# DIO.net
KiCad netlist of a schematic drawn in Altium Designer
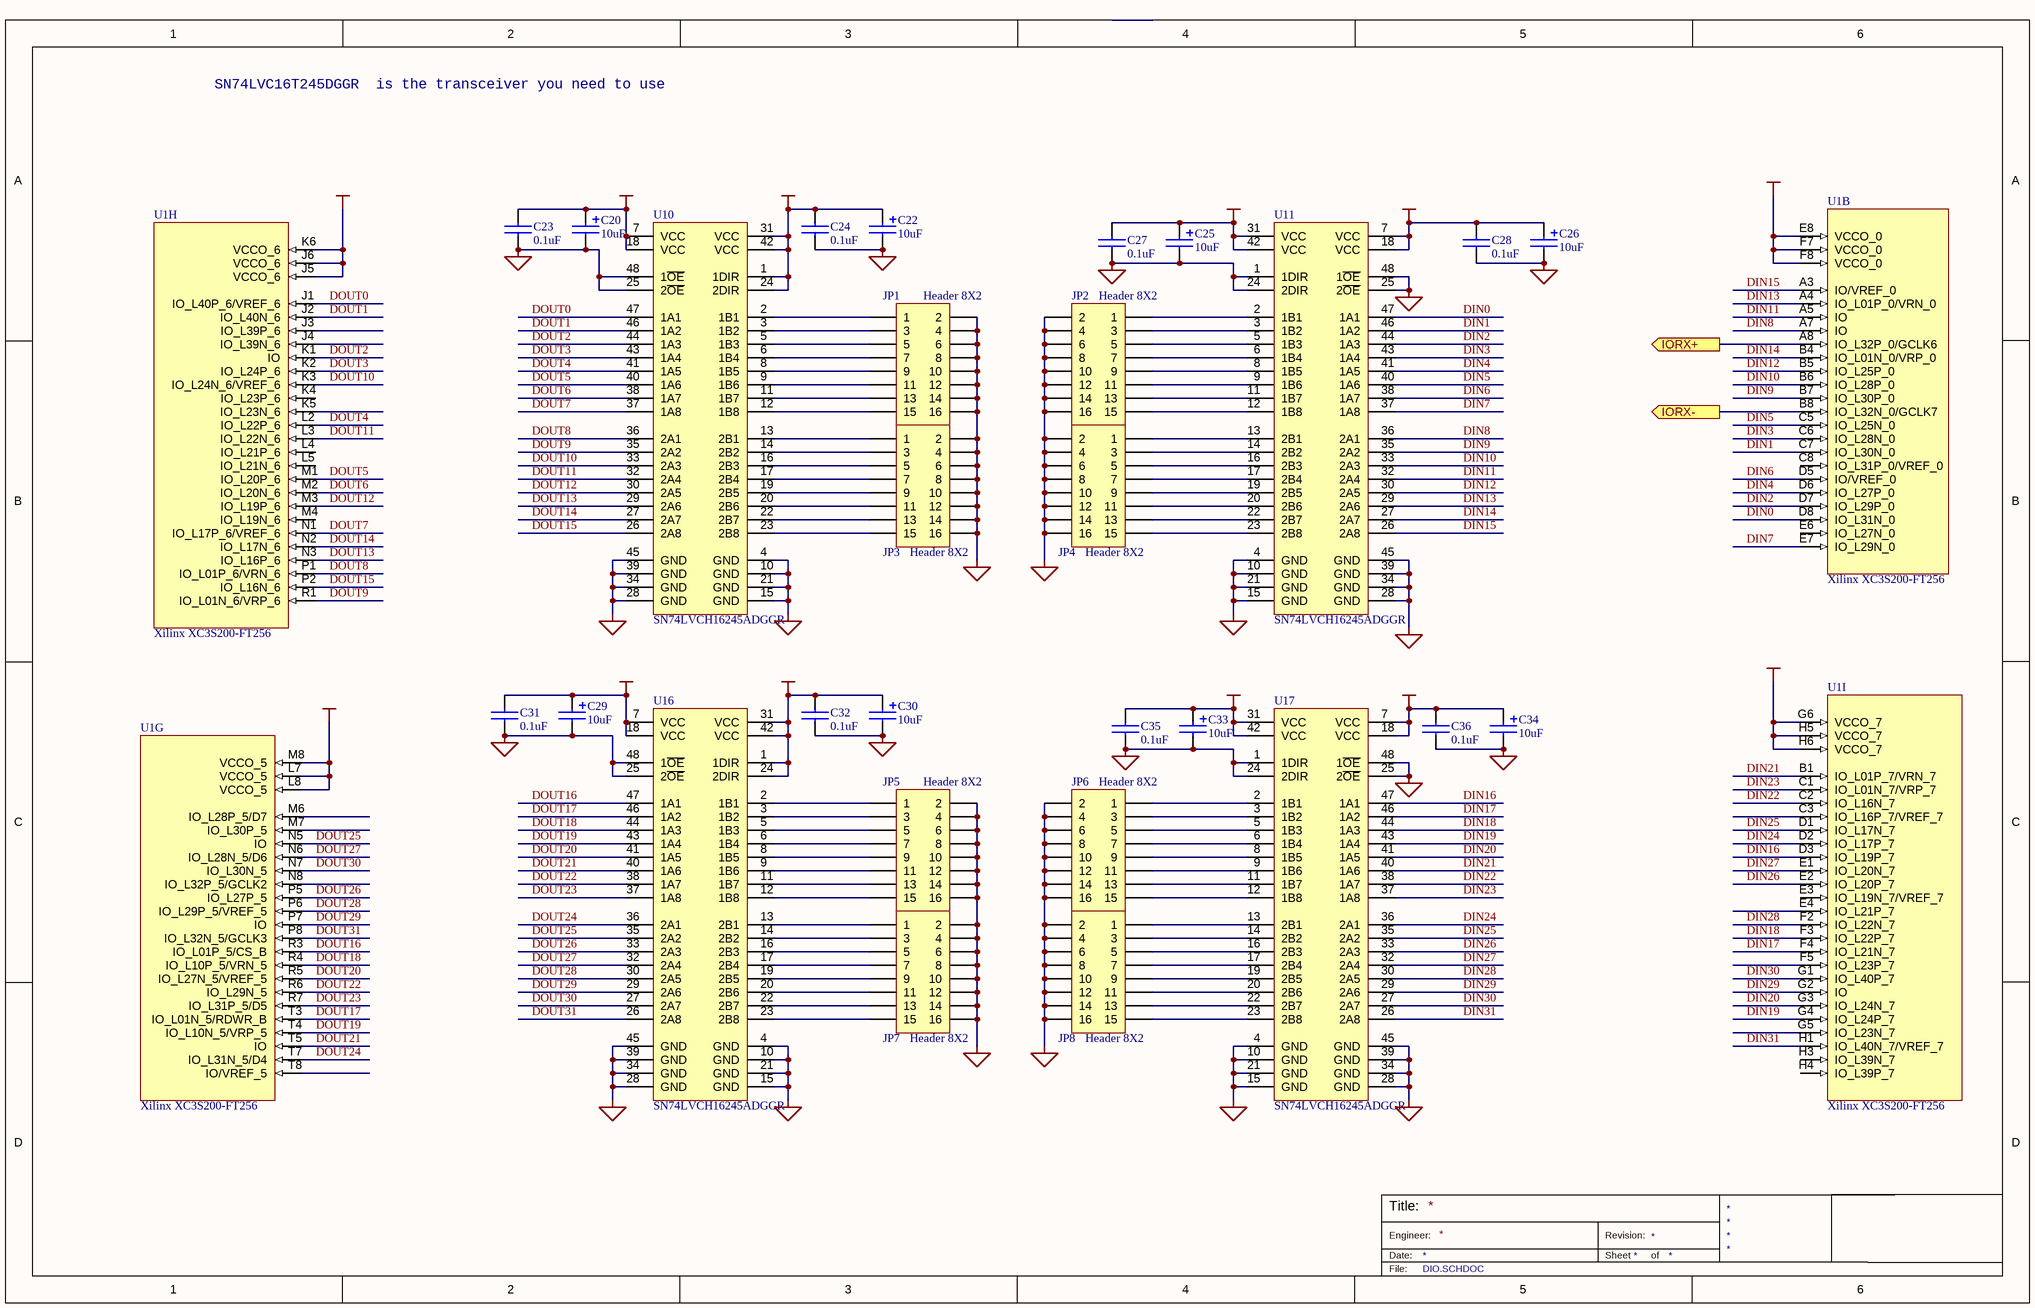
[diagram p0: DIO.SCHDOC]

(export (version "E")
  (design (tool "Eeschema 10.0.6"))
  (components
    (comp (ref "C20")
      (value "10uF")
      (footprint "3216")
      (description "Standard Capacitor")
      (fields (field (name "Comment") "POLCAP"))
      (libsource (lib "parts") (part "POLCAP"))
    )
    (comp (ref "C22")
      (value "10uF")
      (footprint "3216")
      (description "Standard Capacitor")
      (fields (field (name "Comment") "POLCAP"))
      (libsource (lib "parts") (part "POLCAP"))
    )
    (comp (ref "C23")
      (value "0.1uF")
      (footprint "0603")
      (description "Standard Capacitor")
      (fields (field (name "Comment") "CAPACITOR"))
      (libsource (lib "parts") (part "CAPACITOR"))
    )
    (comp (ref "C24")
      (value "0.1uF")
      (footprint "0603")
      (description "Standard Capacitor")
      (fields (field (name "Comment") "CAPACITOR"))
      (libsource (lib "parts") (part "CAPACITOR"))
    )
    (comp (ref "C25")
      (value "10uF")
      (footprint "3216")
      (description "Standard Capacitor")
      (fields (field (name "Comment") "POLCAP"))
      (libsource (lib "parts") (part "POLCAP"))
    )
    (comp (ref "C26")
      (value "10uF")
      (footprint "3216")
      (description "Standard Capacitor")
      (fields (field (name "Comment") "POLCAP"))
      (libsource (lib "parts") (part "POLCAP"))
    )
    (comp (ref "C27")
      (value "0.1uF")
      (footprint "0603")
      (description "Standard Capacitor")
      (fields (field (name "Comment") "CAPACITOR"))
      (libsource (lib "parts") (part "CAPACITOR"))
    )
    (comp (ref "C28")
      (value "0.1uF")
      (footprint "0603")
      (description "Standard Capacitor")
      (fields (field (name "Comment") "CAPACITOR"))
      (libsource (lib "parts") (part "CAPACITOR"))
    )
    (comp (ref "C29")
      (value "10uF")
      (footprint "3216")
      (description "Standard Capacitor")
      (fields (field (name "Comment") "POLCAP"))
      (libsource (lib "parts") (part "POLCAP"))
    )
    (comp (ref "C30")
      (value "10uF")
      (footprint "3216")
      (description "Standard Capacitor")
      (fields (field (name "Comment") "POLCAP"))
      (libsource (lib "parts") (part "POLCAP"))
    )
    (comp (ref "C31")
      (value "0.1uF")
      (footprint "0603")
      (description "Standard Capacitor")
      (fields (field (name "Comment") "CAPACITOR"))
      (libsource (lib "parts") (part "CAPACITOR"))
    )
    (comp (ref "C32")
      (value "0.1uF")
      (footprint "0603")
      (description "Standard Capacitor")
      (fields (field (name "Comment") "CAPACITOR"))
      (libsource (lib "parts") (part "CAPACITOR"))
    )
    (comp (ref "C33")
      (value "10uF")
      (footprint "3216")
      (description "Standard Capacitor")
      (fields (field (name "Comment") "POLCAP"))
      (libsource (lib "parts") (part "POLCAP"))
    )
    (comp (ref "C34")
      (value "10uF")
      (footprint "3216")
      (description "Standard Capacitor")
      (fields (field (name "Comment") "POLCAP"))
      (libsource (lib "parts") (part "POLCAP"))
    )
    (comp (ref "C35")
      (value "0.1uF")
      (footprint "0603")
      (description "Standard Capacitor")
      (fields (field (name "Comment") "CAPACITOR"))
      (libsource (lib "parts") (part "CAPACITOR"))
    )
    (comp (ref "C36")
      (value "0.1uF")
      (footprint "0603")
      (description "Standard Capacitor")
      (fields (field (name "Comment") "CAPACITOR"))
      (libsource (lib "parts") (part "CAPACITOR"))
    )
    (comp (ref "JP1")
      (value "Header 8X2")
      (footprint "HDR2X8")
      (description "Header, 8-Pin, Dual row")
      (fields (field (name "MANUFACTURER") "Generic Components") (field (name "PUBLISHER") "Altium Limited"))
      (libsource (lib "") (part "Header 8X2_1"))
    )
    (comp (ref "JP2")
      (value "Header 8X2")
      (footprint "HDR2X8")
      (description "Header, 8-Pin, Dual row")
      (fields (field (name "MANUFACTURER") "Generic Components") (field (name "PUBLISHER") "Altium Limited"))
      (libsource (lib "Miscellaneous Connectors") (part "Header 8X2"))
    )
    (comp (ref "JP3")
      (value "Header 8X2")
      (footprint "HDR2X8")
      (description "Header, 8-Pin, Dual row")
      (fields (field (name "MANUFACTURER") "Generic Components") (field (name "PUBLISHER") "Altium Limited"))
      (libsource (lib "") (part "Header 8X2_1"))
    )
    (comp (ref "JP4")
      (value "Header 8X2")
      (footprint "HDR2X8")
      (description "Header, 8-Pin, Dual row")
      (fields (field (name "MANUFACTURER") "Generic Components") (field (name "PUBLISHER") "Altium Limited"))
      (libsource (lib "Miscellaneous Connectors") (part "Header 8X2"))
    )
    (comp (ref "JP5")
      (value "Header 8X2")
      (footprint "HDR2X8")
      (description "Header, 8-Pin, Dual row")
      (fields (field (name "MANUFACTURER") "Generic Components") (field (name "PUBLISHER") "Altium Limited"))
      (libsource (lib "") (part "Header 8X2_1"))
    )
    (comp (ref "JP6")
      (value "Header 8X2")
      (footprint "HDR2X8")
      (description "Header, 8-Pin, Dual row")
      (fields (field (name "MANUFACTURER") "Generic Components") (field (name "PUBLISHER") "Altium Limited"))
      (libsource (lib "Miscellaneous Connectors") (part "Header 8X2"))
    )
    (comp (ref "JP7")
      (value "Header 8X2")
      (footprint "HDR2X8")
      (description "Header, 8-Pin, Dual row")
      (fields (field (name "MANUFACTURER") "Generic Components") (field (name "PUBLISHER") "Altium Limited"))
      (libsource (lib "") (part "Header 8X2_1"))
    )
    (comp (ref "JP8")
      (value "Header 8X2")
      (footprint "HDR2X8")
      (description "Header, 8-Pin, Dual row")
      (fields (field (name "MANUFACTURER") "Generic Components") (field (name "PUBLISHER") "Altium Limited"))
      (libsource (lib "Miscellaneous Connectors") (part "Header 8X2"))
    )
    (comp (ref "U1")
      (value "Xilinx XC3S200-FT256")
      (footprint "Xilinx FT256 BGA")
      (description "Xilinx Spartan-3 FPGA")
      (libsource (lib "") (part "XC3S200-FT256_1"))
    )
    (comp (ref "U10")
      (value "SN74LVCH16245ADGGR")
      (footprint "TSSO12x8-G48/X.3")
      (description "16-bit bus transceiver with 3-state outputs")
      (libsource (lib "") (part "SN74LVCH16245ADGGR_1"))
    )
    (comp (ref "U11")
      (value "SN74LVCH16245ADGGR")
      (footprint "TSSO12x8-G48/X.3")
      (description "16-bit bus transceiver with 3-state outputs")
      (libsource (lib "parts") (part "SN74LVCH16245ADGGR"))
    )
    (comp (ref "U16")
      (value "SN74LVCH16245ADGGR")
      (footprint "TSSO12x8-G48/X.3")
      (description "16-bit bus transceiver with 3-state outputs")
      (libsource (lib "") (part "SN74LVCH16245ADGGR_1"))
    )
    (comp (ref "U17")
      (value "SN74LVCH16245ADGGR")
      (footprint "TSSO12x8-G48/X.3")
      (description "16-bit bus transceiver with 3-state outputs")
      (libsource (lib "parts") (part "SN74LVCH16245ADGGR"))
    )
  )
  (nets
    (net (code "1") (name "+2.5VCC") (class "Default")
      (node (ref "C22") (pin "1") (pintype "passive"))
      (node (ref "C24") (pin "1") (pintype "passive"))
      (node (ref "C25") (pin "1") (pintype "passive"))
      (node (ref "C27") (pin "1") (pintype "passive"))
      (node (ref "C30") (pin "1") (pintype "passive"))
      (node (ref "C32") (pin "1") (pintype "passive"))
      (node (ref "C33") (pin "1") (pintype "passive"))
      (node (ref "C35") (pin "1") (pintype "passive"))
      (node (ref "U1") (pin "E8") (pinfunction "VCCO_0_E8") (pintype "input"))
      (node (ref "U1") (pin "F7") (pinfunction "VCCO_0_F7") (pintype "input"))
      (node (ref "U1") (pin "F8") (pinfunction "VCCO_0_F8") (pintype "input"))
      (node (ref "U1") (pin "G6") (pinfunction "VCCO_7_G6") (pintype "input"))
      (node (ref "U1") (pin "H5") (pinfunction "VCCO_7_H5") (pintype "input"))
      (node (ref "U1") (pin "H6") (pinfunction "VCCO_7_H6") (pintype "input"))
      (node (ref "U1") (pin "J5") (pinfunction "VCCO_6_J5") (pintype "input"))
      (node (ref "U1") (pin "J6") (pinfunction "VCCO_6_J6") (pintype "input"))
      (node (ref "U1") (pin "K6") (pinfunction "VCCO_6_K6") (pintype "input"))
      (node (ref "U1") (pin "L7") (pinfunction "VCCO_5_L7") (pintype "input"))
      (node (ref "U1") (pin "L8") (pinfunction "VCCO_5_L8") (pintype "input"))
      (node (ref "U1") (pin "M8") (pinfunction "VCCO_5_M8") (pintype "input"))
      (node (ref "U10") (pin "1") (pinfunction "1DIR_1") (pintype "passive"))
      (node (ref "U10") (pin "24") (pinfunction "2DIR_24") (pintype "passive"))
      (node (ref "U10") (pin "31") (pinfunction "VCC_31") (pintype "power_in"))
      (node (ref "U10") (pin "42") (pinfunction "VCC_42") (pintype "power_in"))
      (node (ref "U11") (pin "31") (pinfunction "VCC_31") (pintype "power_in"))
      (node (ref "U11") (pin "42") (pinfunction "VCC_42") (pintype "power_in"))
      (node (ref "U16") (pin "1") (pinfunction "1DIR_1") (pintype "passive"))
      (node (ref "U16") (pin "24") (pinfunction "2DIR_24") (pintype "passive"))
      (node (ref "U16") (pin "31") (pinfunction "VCC_31") (pintype "power_in"))
      (node (ref "U16") (pin "42") (pinfunction "VCC_42") (pintype "power_in"))
      (node (ref "U17") (pin "31") (pinfunction "VCC_31") (pintype "power_in"))
      (node (ref "U17") (pin "42") (pinfunction "VCC_42") (pintype "power_in"))
    )
    (net (code "2") (name "+5VCC") (class "Default")
      (node (ref "C20") (pin "1") (pintype "passive"))
      (node (ref "C23") (pin "1") (pintype "passive"))
      (node (ref "C26") (pin "1") (pintype "passive"))
      (node (ref "C28") (pin "1") (pintype "passive"))
      (node (ref "C29") (pin "1") (pintype "passive"))
      (node (ref "C31") (pin "1") (pintype "passive"))
      (node (ref "C34") (pin "1") (pintype "passive"))
      (node (ref "C36") (pin "1") (pintype "passive"))
      (node (ref "U10") (pin "18") (pinfunction "VCC_18") (pintype "power_in"))
      (node (ref "U10") (pin "7") (pinfunction "VCC_7") (pintype "power_in"))
      (node (ref "U11") (pin "18") (pinfunction "VCC_18") (pintype "power_in"))
      (node (ref "U11") (pin "7") (pinfunction "VCC_7") (pintype "power_in"))
      (node (ref "U16") (pin "18") (pinfunction "VCC_18") (pintype "power_in"))
      (node (ref "U16") (pin "7") (pinfunction "VCC_7") (pintype "power_in"))
      (node (ref "U17") (pin "18") (pinfunction "VCC_18") (pintype "power_in"))
      (node (ref "U17") (pin "7") (pinfunction "VCC_7") (pintype "power_in"))
    )
    (net (code "3") (name "/DIN0") (class "Default")
      (node (ref "U1") (pin "D8") (pinfunction "IO_L31N_0_D8") (pintype "input"))
      (node (ref "U11") (pin "47") (pinfunction "1A1_47") (pintype "passive"))
    )
    (net (code "4") (name "/DIN1") (class "Default")
      (node (ref "U1") (pin "C7") (pinfunction "IO_L30N_0_C7") (pintype "input"))
      (node (ref "U11") (pin "46") (pinfunction "1A2_46") (pintype "passive"))
    )
    (net (code "5") (name "/DIN2") (class "Default")
      (node (ref "U1") (pin "D7") (pinfunction "IO_L29P_0_D7") (pintype "input"))
      (node (ref "U11") (pin "44") (pinfunction "1A3_44") (pintype "passive"))
    )
    (net (code "6") (name "/DIN3") (class "Default")
      (node (ref "U1") (pin "C6") (pinfunction "IO_L28N_0_C6") (pintype "input"))
      (node (ref "U11") (pin "43") (pinfunction "1A4_43") (pintype "passive"))
    )
    (net (code "7") (name "/DIN4") (class "Default")
      (node (ref "U1") (pin "D6") (pinfunction "IO_L27P_0_D6") (pintype "input"))
      (node (ref "U11") (pin "41") (pinfunction "1A5_41") (pintype "passive"))
    )
    (net (code "8") (name "/DIN5") (class "Default")
      (node (ref "U1") (pin "C5") (pinfunction "IO_L25N_0_C5") (pintype "input"))
      (node (ref "U11") (pin "40") (pinfunction "1A6_40") (pintype "passive"))
    )
    (net (code "9") (name "/DIN6") (class "Default")
      (node (ref "U1") (pin "D5") (pinfunction "IO/VREF_0_D5") (pintype "input"))
      (node (ref "U11") (pin "38") (pinfunction "1A7_38") (pintype "passive"))
    )
    (net (code "10") (name "/DIN7") (class "Default")
      (node (ref "U1") (pin "E7") (pinfunction "IO_L29N_0_E7") (pintype "input"))
      (node (ref "U11") (pin "37") (pinfunction "1A8_37") (pintype "passive"))
    )
    (net (code "11") (name "/DIN8") (class "Default")
      (node (ref "U1") (pin "A7") (pinfunction "IO_A7") (pintype "input"))
      (node (ref "U11") (pin "36") (pinfunction "2A1_36") (pintype "passive"))
    )
    (net (code "12") (name "/DIN9") (class "Default")
      (node (ref "U1") (pin "B7") (pinfunction "IO_L30P_0_B7") (pintype "input"))
      (node (ref "U11") (pin "35") (pinfunction "2A2_35") (pintype "passive"))
    )
    (net (code "13") (name "/DIN10") (class "Default")
      (node (ref "U1") (pin "B6") (pinfunction "IO_L28P_0_B6") (pintype "input"))
      (node (ref "U11") (pin "33") (pinfunction "2A3_33") (pintype "passive"))
    )
    (net (code "14") (name "/DIN11") (class "Default")
      (node (ref "U1") (pin "A5") (pinfunction "IO_A5") (pintype "input"))
      (node (ref "U11") (pin "32") (pinfunction "2A4_32") (pintype "passive"))
    )
    (net (code "15") (name "/DIN12") (class "Default")
      (node (ref "U1") (pin "B5") (pinfunction "IO_L25P_0_B5") (pintype "input"))
      (node (ref "U11") (pin "30") (pinfunction "2A5_30") (pintype "passive"))
    )
    (net (code "16") (name "/DIN13") (class "Default")
      (node (ref "U1") (pin "A4") (pinfunction "IO_L01P_0/VRN_0_A4") (pintype "input"))
      (node (ref "U11") (pin "29") (pinfunction "2A6_29") (pintype "passive"))
    )
    (net (code "17") (name "/DIN14") (class "Default")
      (node (ref "U1") (pin "B4") (pinfunction "IO_L01N_0/VRP_0_B4") (pintype "input"))
      (node (ref "U11") (pin "27") (pinfunction "2A7_27") (pintype "passive"))
    )
    (net (code "18") (name "/DIN15") (class "Default")
      (node (ref "U1") (pin "A3") (pinfunction "IO/VREF_0_A3") (pintype "input"))
      (node (ref "U11") (pin "26") (pinfunction "2A8_26") (pintype "passive"))
    )
    (net (code "19") (name "/DIN16") (class "Default")
      (node (ref "U1") (pin "D3") (pinfunction "IO_L19P_7_D3") (pintype "input"))
      (node (ref "U17") (pin "47") (pinfunction "1A1_47") (pintype "passive"))
    )
    (net (code "20") (name "/DIN17") (class "Default")
      (node (ref "U1") (pin "F4") (pinfunction "IO_L21N_7_F4") (pintype "input"))
      (node (ref "U17") (pin "46") (pinfunction "1A2_46") (pintype "passive"))
    )
    (net (code "21") (name "/DIN18") (class "Default")
      (node (ref "U1") (pin "F3") (pinfunction "IO_L22P_7_F3") (pintype "input"))
      (node (ref "U17") (pin "44") (pinfunction "1A3_44") (pintype "passive"))
    )
    (net (code "22") (name "/DIN19") (class "Default")
      (node (ref "U1") (pin "G4") (pinfunction "IO_L24P_7_G4") (pintype "input"))
      (node (ref "U17") (pin "43") (pinfunction "1A4_43") (pintype "passive"))
    )
    (net (code "23") (name "/DIN20") (class "Default")
      (node (ref "U1") (pin "G3") (pinfunction "IO_L24N_7_G3") (pintype "input"))
      (node (ref "U17") (pin "41") (pinfunction "1A5_41") (pintype "passive"))
    )
    (net (code "24") (name "/DIN21") (class "Default")
      (node (ref "U1") (pin "B1") (pinfunction "IO_L01P_7/VRN_7_B1") (pintype "input"))
      (node (ref "U17") (pin "40") (pinfunction "1A6_40") (pintype "passive"))
    )
    (net (code "25") (name "/DIN22") (class "Default")
      (node (ref "U1") (pin "C2") (pinfunction "IO_L16N_7_C2") (pintype "input"))
      (node (ref "U17") (pin "38") (pinfunction "1A7_38") (pintype "passive"))
    )
    (net (code "26") (name "/DIN23") (class "Default")
      (node (ref "U1") (pin "C1") (pinfunction "IO_L01N_7/VRP_7_C1") (pintype "input"))
      (node (ref "U17") (pin "37") (pinfunction "1A8_37") (pintype "passive"))
    )
    (net (code "27") (name "/DIN24") (class "Default")
      (node (ref "U1") (pin "D2") (pinfunction "IO_L17P_7_D2") (pintype "input"))
      (node (ref "U17") (pin "36") (pinfunction "2A1_36") (pintype "passive"))
    )
    (net (code "28") (name "/DIN25") (class "Default")
      (node (ref "U1") (pin "D1") (pinfunction "IO_L17N_7_D1") (pintype "input"))
      (node (ref "U17") (pin "35") (pinfunction "2A2_35") (pintype "passive"))
    )
    (net (code "29") (name "/DIN26") (class "Default")
      (node (ref "U1") (pin "E2") (pinfunction "IO_L20P_7_E2") (pintype "input"))
      (node (ref "U17") (pin "33") (pinfunction "2A3_33") (pintype "passive"))
    )
    (net (code "30") (name "/DIN27") (class "Default")
      (node (ref "U1") (pin "E1") (pinfunction "IO_L20N_7_E1") (pintype "input"))
      (node (ref "U17") (pin "32") (pinfunction "2A4_32") (pintype "passive"))
    )
    (net (code "31") (name "/DIN28") (class "Default")
      (node (ref "U1") (pin "F2") (pinfunction "IO_L22N_7_F2") (pintype "input"))
      (node (ref "U17") (pin "30") (pinfunction "2A5_30") (pintype "passive"))
    )
    (net (code "32") (name "/DIN29") (class "Default")
      (node (ref "U1") (pin "G2") (pinfunction "IO_G2") (pintype "input"))
      (node (ref "U17") (pin "29") (pinfunction "2A6_29") (pintype "passive"))
    )
    (net (code "33") (name "/DIN30") (class "Default")
      (node (ref "U1") (pin "G1") (pinfunction "IO_L40P_7_G1") (pintype "input"))
      (node (ref "U17") (pin "27") (pinfunction "2A7_27") (pintype "passive"))
    )
    (net (code "34") (name "/DIN31") (class "Default")
      (node (ref "U1") (pin "H1") (pinfunction "IO_L40N_7/VREF_7_H1") (pintype "input"))
      (node (ref "U17") (pin "26") (pinfunction "2A8_26") (pintype "passive"))
    )
    (net (code "35") (name "/DOUT0") (class "Default")
      (node (ref "U1") (pin "J1") (pinfunction "IO_L40P_6/VREF_6_J1") (pintype "input"))
      (node (ref "U10") (pin "47") (pinfunction "1A1_47") (pintype "passive"))
    )
    (net (code "36") (name "/DOUT1") (class "Default")
      (node (ref "U1") (pin "J2") (pinfunction "IO_L40N_6_J2") (pintype "input"))
      (node (ref "U10") (pin "46") (pinfunction "1A2_46") (pintype "passive"))
    )
    (net (code "37") (name "/DOUT2") (class "Default")
      (node (ref "U1") (pin "K1") (pinfunction "IO_K1") (pintype "input"))
      (node (ref "U10") (pin "44") (pinfunction "1A3_44") (pintype "passive"))
    )
    (net (code "38") (name "/DOUT3") (class "Default")
      (node (ref "U1") (pin "K2") (pinfunction "IO_L24P_6_K2") (pintype "input"))
      (node (ref "U10") (pin "43") (pinfunction "1A4_43") (pintype "passive"))
    )
    (net (code "39") (name "/DOUT4") (class "Default")
      (node (ref "U1") (pin "L2") (pinfunction "IO_L22P_6_L2") (pintype "input"))
      (node (ref "U10") (pin "41") (pinfunction "1A5_41") (pintype "passive"))
    )
    (net (code "40") (name "/DOUT5") (class "Default")
      (node (ref "U1") (pin "M1") (pinfunction "IO_L20P_6_M1") (pintype "input"))
      (node (ref "U10") (pin "40") (pinfunction "1A6_40") (pintype "passive"))
    )
    (net (code "41") (name "/DOUT6") (class "Default")
      (node (ref "U1") (pin "M2") (pinfunction "IO_L20N_6_M2") (pintype "input"))
      (node (ref "U10") (pin "38") (pinfunction "1A7_38") (pintype "passive"))
    )
    (net (code "42") (name "/DOUT7") (class "Default")
      (node (ref "U1") (pin "N1") (pinfunction "IO_L17P_6/VREF_6_N1") (pintype "input"))
      (node (ref "U10") (pin "37") (pinfunction "1A8_37") (pintype "passive"))
    )
    (net (code "43") (name "/DOUT8") (class "Default")
      (node (ref "U1") (pin "P1") (pinfunction "IO_L01P_6/VRN_6_P1") (pintype "input"))
      (node (ref "U10") (pin "36") (pinfunction "2A1_36") (pintype "passive"))
    )
    (net (code "44") (name "/DOUT9") (class "Default")
      (node (ref "U1") (pin "R1") (pinfunction "IO_L01N_6/VRP_6_R1") (pintype "input"))
      (node (ref "U10") (pin "35") (pinfunction "2A2_35") (pintype "passive"))
    )
    (net (code "45") (name "/DOUT10") (class "Default")
      (node (ref "U1") (pin "K3") (pinfunction "IO_L24N_6/VREF_6_K3") (pintype "input"))
      (node (ref "U10") (pin "33") (pinfunction "2A3_33") (pintype "passive"))
    )
    (net (code "46") (name "/DOUT11") (class "Default")
      (node (ref "U1") (pin "L3") (pinfunction "IO_L22N_6_L3") (pintype "input"))
      (node (ref "U10") (pin "32") (pinfunction "2A4_32") (pintype "passive"))
    )
    (net (code "47") (name "/DOUT12") (class "Default")
      (node (ref "U1") (pin "M3") (pinfunction "IO_L19P_6_M3") (pintype "input"))
      (node (ref "U10") (pin "30") (pinfunction "2A5_30") (pintype "passive"))
    )
    (net (code "48") (name "/DOUT13") (class "Default")
      (node (ref "U1") (pin "N3") (pinfunction "IO_L16P_6_N3") (pintype "input"))
      (node (ref "U10") (pin "29") (pinfunction "2A6_29") (pintype "passive"))
    )
    (net (code "49") (name "/DOUT14") (class "Default")
      (node (ref "U1") (pin "N2") (pinfunction "IO_L17N_6_N2") (pintype "input"))
      (node (ref "U10") (pin "27") (pinfunction "2A7_27") (pintype "passive"))
    )
    (net (code "50") (name "/DOUT15") (class "Default")
      (node (ref "U1") (pin "P2") (pinfunction "IO_L16N_6_P2") (pintype "input"))
      (node (ref "U10") (pin "26") (pinfunction "2A8_26") (pintype "passive"))
    )
    (net (code "51") (name "/DOUT16") (class "Default")
      (node (ref "U1") (pin "R3") (pinfunction "IO_L01P_5/CS_B_R3") (pintype "input"))
      (node (ref "U16") (pin "47") (pinfunction "1A1_47") (pintype "passive"))
    )
    (net (code "52") (name "/DOUT17") (class "Default")
      (node (ref "U1") (pin "T3") (pinfunction "IO_L01N_5/RDWR_B_T3") (pintype "input"))
      (node (ref "U16") (pin "46") (pinfunction "1A2_46") (pintype "passive"))
    )
    (net (code "53") (name "/DOUT18") (class "Default")
      (node (ref "U1") (pin "R4") (pinfunction "IO_L10P_5/VRN_5_R4") (pintype "input"))
      (node (ref "U16") (pin "44") (pinfunction "1A3_44") (pintype "passive"))
    )
    (net (code "54") (name "/DOUT19") (class "Default")
      (node (ref "U1") (pin "T4") (pinfunction "IO_L10N_5/VRP_5_T4") (pintype "input"))
      (node (ref "U16") (pin "43") (pinfunction "1A4_43") (pintype "passive"))
    )
    (net (code "55") (name "/DOUT20") (class "Default")
      (node (ref "U1") (pin "R5") (pinfunction "IO_L27N_5/VREF_5_R5") (pintype "input"))
      (node (ref "U16") (pin "41") (pinfunction "1A5_41") (pintype "passive"))
    )
    (net (code "56") (name "/DOUT21") (class "Default")
      (node (ref "U1") (pin "T5") (pinfunction "IO_T5") (pintype "input"))
      (node (ref "U16") (pin "40") (pinfunction "1A6_40") (pintype "passive"))
    )
    (net (code "57") (name "/DOUT22") (class "Default")
      (node (ref "U1") (pin "R6") (pinfunction "IO_L29N_5_R6") (pintype "input"))
      (node (ref "U16") (pin "38") (pinfunction "1A7_38") (pintype "passive"))
    )
    (net (code "58") (name "/DOUT23") (class "Default")
      (node (ref "U1") (pin "R7") (pinfunction "IO_L31P_5/D5_R7") (pintype "input"))
      (node (ref "U16") (pin "37") (pinfunction "1A8_37") (pintype "passive"))
    )
    (net (code "59") (name "/DOUT24") (class "Default")
      (node (ref "U1") (pin "T7") (pinfunction "IO_L31N_5/D4_T7") (pintype "input"))
      (node (ref "U16") (pin "36") (pinfunction "2A1_36") (pintype "passive"))
    )
    (net (code "60") (name "/DOUT25") (class "Default")
      (node (ref "U1") (pin "N5") (pinfunction "IO_N5") (pintype "input"))
      (node (ref "U16") (pin "35") (pinfunction "2A2_35") (pintype "passive"))
    )
    (net (code "61") (name "/DOUT26") (class "Default")
      (node (ref "U1") (pin "P5") (pinfunction "IO_L27P_5_P5") (pintype "input"))
      (node (ref "U16") (pin "33") (pinfunction "2A3_33") (pintype "passive"))
    )
    (net (code "62") (name "/DOUT27") (class "Default")
      (node (ref "U1") (pin "N6") (pinfunction "IO_L28N_5/D6_N6") (pintype "input"))
      (node (ref "U16") (pin "32") (pinfunction "2A4_32") (pintype "passive"))
    )
    (net (code "63") (name "/DOUT28") (class "Default")
      (node (ref "U1") (pin "P6") (pinfunction "IO_L29P_5/VREF_5_P6") (pintype "input"))
      (node (ref "U16") (pin "30") (pinfunction "2A5_30") (pintype "passive"))
    )
    (net (code "64") (name "/DOUT29") (class "Default")
      (node (ref "U1") (pin "P7") (pinfunction "IO_P7") (pintype "input"))
      (node (ref "U16") (pin "29") (pinfunction "2A6_29") (pintype "passive"))
    )
    (net (code "65") (name "/DOUT30") (class "Default")
      (node (ref "U1") (pin "N7") (pinfunction "IO_L30N_5_N7") (pintype "input"))
      (node (ref "U16") (pin "27") (pinfunction "2A7_27") (pintype "passive"))
    )
    (net (code "66") (name "/DOUT31") (class "Default")
      (node (ref "U1") (pin "P8") (pinfunction "IO_L32N_5/GCLK3_P8") (pintype "input"))
      (node (ref "U16") (pin "26") (pinfunction "2A8_26") (pintype "passive"))
    )
    (net (code "67") (name "/IORX+") (class "Default")
      (node (ref "U1") (pin "A8") (pinfunction "IO_L32P_0/GCLK6_A8") (pintype "input"))
    )
    (net (code "68") (name "/IORX-") (class "Default")
      (node (ref "U1") (pin "B8") (pinfunction "IO_L32N_0/GCLK7_B8") (pintype "input"))
    )
    (net (code "69") (name "GND") (class "Default")
      (node (ref "C20") (pin "2") (pintype "passive"))
      (node (ref "C22") (pin "2") (pintype "passive"))
      (node (ref "C23") (pin "2") (pintype "passive"))
      (node (ref "C24") (pin "2") (pintype "passive"))
      (node (ref "C25") (pin "2") (pintype "passive"))
      (node (ref "C26") (pin "2") (pintype "passive"))
      (node (ref "C27") (pin "2") (pintype "passive"))
      (node (ref "C28") (pin "2") (pintype "passive"))
      (node (ref "C29") (pin "2") (pintype "passive"))
      (node (ref "C30") (pin "2") (pintype "passive"))
      (node (ref "C31") (pin "2") (pintype "passive"))
      (node (ref "C32") (pin "2") (pintype "passive"))
      (node (ref "C33") (pin "2") (pintype "passive"))
      (node (ref "C34") (pin "2") (pintype "passive"))
      (node (ref "C35") (pin "2") (pintype "passive"))
      (node (ref "C36") (pin "2") (pintype "passive"))
      (node (ref "JP1") (pin "10") (pinfunction "10_10") (pintype "passive"))
      (node (ref "JP1") (pin "12") (pinfunction "12_12") (pintype "passive"))
      (node (ref "JP1") (pin "14") (pinfunction "14_14") (pintype "passive"))
      (node (ref "JP1") (pin "16") (pinfunction "16_16") (pintype "passive"))
      (node (ref "JP1") (pin "2") (pinfunction "2_2") (pintype "passive"))
      (node (ref "JP1") (pin "4") (pinfunction "4_4") (pintype "passive"))
      (node (ref "JP1") (pin "6") (pinfunction "6_6") (pintype "passive"))
      (node (ref "JP1") (pin "8") (pinfunction "8_8") (pintype "passive"))
      (node (ref "JP2") (pin "10") (pinfunction "10_10") (pintype "passive"))
      (node (ref "JP2") (pin "12") (pinfunction "12_12") (pintype "passive"))
      (node (ref "JP2") (pin "14") (pinfunction "14_14") (pintype "passive"))
      (node (ref "JP2") (pin "16") (pinfunction "16_16") (pintype "passive"))
      (node (ref "JP2") (pin "2") (pinfunction "2_2") (pintype "passive"))
      (node (ref "JP2") (pin "4") (pinfunction "4_4") (pintype "passive"))
      (node (ref "JP2") (pin "6") (pinfunction "6_6") (pintype "passive"))
      (node (ref "JP2") (pin "8") (pinfunction "8_8") (pintype "passive"))
      (node (ref "JP3") (pin "10") (pinfunction "10_10") (pintype "passive"))
      (node (ref "JP3") (pin "12") (pinfunction "12_12") (pintype "passive"))
      (node (ref "JP3") (pin "14") (pinfunction "14_14") (pintype "passive"))
      (node (ref "JP3") (pin "16") (pinfunction "16_16") (pintype "passive"))
      (node (ref "JP3") (pin "2") (pinfunction "2_2") (pintype "passive"))
      (node (ref "JP3") (pin "4") (pinfunction "4_4") (pintype "passive"))
      (node (ref "JP3") (pin "6") (pinfunction "6_6") (pintype "passive"))
      (node (ref "JP3") (pin "8") (pinfunction "8_8") (pintype "passive"))
      (node (ref "JP4") (pin "10") (pinfunction "10_10") (pintype "passive"))
      (node (ref "JP4") (pin "12") (pinfunction "12_12") (pintype "passive"))
      (node (ref "JP4") (pin "14") (pinfunction "14_14") (pintype "passive"))
      (node (ref "JP4") (pin "16") (pinfunction "16_16") (pintype "passive"))
      (node (ref "JP4") (pin "2") (pinfunction "2_2") (pintype "passive"))
      (node (ref "JP4") (pin "4") (pinfunction "4_4") (pintype "passive"))
      (node (ref "JP4") (pin "6") (pinfunction "6_6") (pintype "passive"))
      (node (ref "JP4") (pin "8") (pinfunction "8_8") (pintype "passive"))
      (node (ref "JP5") (pin "10") (pinfunction "10_10") (pintype "passive"))
      (node (ref "JP5") (pin "12") (pinfunction "12_12") (pintype "passive"))
      (node (ref "JP5") (pin "14") (pinfunction "14_14") (pintype "passive"))
      (node (ref "JP5") (pin "16") (pinfunction "16_16") (pintype "passive"))
      (node (ref "JP5") (pin "2") (pinfunction "2_2") (pintype "passive"))
      (node (ref "JP5") (pin "4") (pinfunction "4_4") (pintype "passive"))
      (node (ref "JP5") (pin "6") (pinfunction "6_6") (pintype "passive"))
      (node (ref "JP5") (pin "8") (pinfunction "8_8") (pintype "passive"))
      (node (ref "JP6") (pin "10") (pinfunction "10_10") (pintype "passive"))
      (node (ref "JP6") (pin "12") (pinfunction "12_12") (pintype "passive"))
      (node (ref "JP6") (pin "14") (pinfunction "14_14") (pintype "passive"))
      (node (ref "JP6") (pin "16") (pinfunction "16_16") (pintype "passive"))
      (node (ref "JP6") (pin "2") (pinfunction "2_2") (pintype "passive"))
      (node (ref "JP6") (pin "4") (pinfunction "4_4") (pintype "passive"))
      (node (ref "JP6") (pin "6") (pinfunction "6_6") (pintype "passive"))
      (node (ref "JP6") (pin "8") (pinfunction "8_8") (pintype "passive"))
      (node (ref "JP7") (pin "10") (pinfunction "10_10") (pintype "passive"))
      (node (ref "JP7") (pin "12") (pinfunction "12_12") (pintype "passive"))
      (node (ref "JP7") (pin "14") (pinfunction "14_14") (pintype "passive"))
      (node (ref "JP7") (pin "16") (pinfunction "16_16") (pintype "passive"))
      (node (ref "JP7") (pin "2") (pinfunction "2_2") (pintype "passive"))
      (node (ref "JP7") (pin "4") (pinfunction "4_4") (pintype "passive"))
      (node (ref "JP7") (pin "6") (pinfunction "6_6") (pintype "passive"))
      (node (ref "JP7") (pin "8") (pinfunction "8_8") (pintype "passive"))
      (node (ref "JP8") (pin "10") (pinfunction "10_10") (pintype "passive"))
      (node (ref "JP8") (pin "12") (pinfunction "12_12") (pintype "passive"))
      (node (ref "JP8") (pin "14") (pinfunction "14_14") (pintype "passive"))
      (node (ref "JP8") (pin "16") (pinfunction "16_16") (pintype "passive"))
      (node (ref "JP8") (pin "2") (pinfunction "2_2") (pintype "passive"))
      (node (ref "JP8") (pin "4") (pinfunction "4_4") (pintype "passive"))
      (node (ref "JP8") (pin "6") (pinfunction "6_6") (pintype "passive"))
      (node (ref "JP8") (pin "8") (pinfunction "8_8") (pintype "passive"))
      (node (ref "U10") (pin "10") (pinfunction "GND_10") (pintype "power_in"))
      (node (ref "U10") (pin "15") (pinfunction "GND_15") (pintype "power_in"))
      (node (ref "U10") (pin "21") (pinfunction "GND_21") (pintype "power_in"))
      (node (ref "U10") (pin "25") (pinfunction "2~{OE}_25") (pintype "passive"))
      (node (ref "U10") (pin "28") (pinfunction "GND_28") (pintype "power_in"))
      (node (ref "U10") (pin "34") (pinfunction "GND_34") (pintype "power_in"))
      (node (ref "U10") (pin "39") (pinfunction "GND_39") (pintype "power_in"))
      (node (ref "U10") (pin "4") (pinfunction "GND_4") (pintype "power_in"))
      (node (ref "U10") (pin "45") (pinfunction "GND_45") (pintype "power_in"))
      (node (ref "U10") (pin "48") (pinfunction "1~{OE}_48") (pintype "passive"))
      (node (ref "U11") (pin "1") (pinfunction "1DIR_1") (pintype "passive"))
      (node (ref "U11") (pin "10") (pinfunction "GND_10") (pintype "power_in"))
      (node (ref "U11") (pin "15") (pinfunction "GND_15") (pintype "power_in"))
      (node (ref "U11") (pin "21") (pinfunction "GND_21") (pintype "power_in"))
      (node (ref "U11") (pin "24") (pinfunction "2DIR_24") (pintype "passive"))
      (node (ref "U11") (pin "25") (pinfunction "2~{OE}_25") (pintype "passive"))
      (node (ref "U11") (pin "28") (pinfunction "GND_28") (pintype "power_in"))
      (node (ref "U11") (pin "34") (pinfunction "GND_34") (pintype "power_in"))
      (node (ref "U11") (pin "39") (pinfunction "GND_39") (pintype "power_in"))
      (node (ref "U11") (pin "4") (pinfunction "GND_4") (pintype "power_in"))
      (node (ref "U11") (pin "45") (pinfunction "GND_45") (pintype "power_in"))
      (node (ref "U11") (pin "48") (pinfunction "1~{OE}_48") (pintype "passive"))
      (node (ref "U16") (pin "10") (pinfunction "GND_10") (pintype "power_in"))
      (node (ref "U16") (pin "15") (pinfunction "GND_15") (pintype "power_in"))
      (node (ref "U16") (pin "21") (pinfunction "GND_21") (pintype "power_in"))
      (node (ref "U16") (pin "25") (pinfunction "2~{OE}_25") (pintype "passive"))
      (node (ref "U16") (pin "28") (pinfunction "GND_28") (pintype "power_in"))
      (node (ref "U16") (pin "34") (pinfunction "GND_34") (pintype "power_in"))
      (node (ref "U16") (pin "39") (pinfunction "GND_39") (pintype "power_in"))
      (node (ref "U16") (pin "4") (pinfunction "GND_4") (pintype "power_in"))
      (node (ref "U16") (pin "45") (pinfunction "GND_45") (pintype "power_in"))
      (node (ref "U16") (pin "48") (pinfunction "1~{OE}_48") (pintype "passive"))
      (node (ref "U17") (pin "1") (pinfunction "1DIR_1") (pintype "passive"))
      (node (ref "U17") (pin "10") (pinfunction "GND_10") (pintype "power_in"))
      (node (ref "U17") (pin "15") (pinfunction "GND_15") (pintype "power_in"))
      (node (ref "U17") (pin "21") (pinfunction "GND_21") (pintype "power_in"))
      (node (ref "U17") (pin "24") (pinfunction "2DIR_24") (pintype "passive"))
      (node (ref "U17") (pin "25") (pinfunction "2~{OE}_25") (pintype "passive"))
      (node (ref "U17") (pin "28") (pinfunction "GND_28") (pintype "power_in"))
      (node (ref "U17") (pin "34") (pinfunction "GND_34") (pintype "power_in"))
      (node (ref "U17") (pin "39") (pinfunction "GND_39") (pintype "power_in"))
      (node (ref "U17") (pin "4") (pinfunction "GND_4") (pintype "power_in"))
      (node (ref "U17") (pin "45") (pinfunction "GND_45") (pintype "power_in"))
      (node (ref "U17") (pin "48") (pinfunction "1~{OE}_48") (pintype "passive"))
    )
    (net (code "70") (name "Net-(U10-1B1)") (class "Default")
      (node (ref "JP1") (pin "1") (pinfunction "1_1") (pintype "passive"))
      (node (ref "U10") (pin "2") (pinfunction "1B1_2") (pintype "passive"))
    )
    (net (code "71") (name "Net-(U10-1B2)") (class "Default")
      (node (ref "JP1") (pin "3") (pinfunction "3_3") (pintype "passive"))
      (node (ref "U10") (pin "3") (pinfunction "1B2_3") (pintype "passive"))
    )
    (net (code "72") (name "Net-(U10-1B3)") (class "Default")
      (node (ref "JP1") (pin "5") (pinfunction "5_5") (pintype "passive"))
      (node (ref "U10") (pin "5") (pinfunction "1B3_5") (pintype "passive"))
    )
    (net (code "73") (name "Net-(U10-1B4)") (class "Default")
      (node (ref "JP1") (pin "7") (pinfunction "7_7") (pintype "passive"))
      (node (ref "U10") (pin "6") (pinfunction "1B4_6") (pintype "passive"))
    )
    (net (code "74") (name "Net-(U10-1B5)") (class "Default")
      (node (ref "JP1") (pin "9") (pinfunction "9_9") (pintype "passive"))
      (node (ref "U10") (pin "8") (pinfunction "1B5_8") (pintype "passive"))
    )
    (net (code "75") (name "Net-(U10-1B6)") (class "Default")
      (node (ref "JP1") (pin "11") (pinfunction "11_11") (pintype "passive"))
      (node (ref "U10") (pin "9") (pinfunction "1B6_9") (pintype "passive"))
    )
    (net (code "76") (name "Net-(U10-1B7)") (class "Default")
      (node (ref "JP1") (pin "13") (pinfunction "13_13") (pintype "passive"))
      (node (ref "U10") (pin "11") (pinfunction "1B7_11") (pintype "passive"))
    )
    (net (code "77") (name "Net-(U10-1B8)") (class "Default")
      (node (ref "JP1") (pin "15") (pinfunction "15_15") (pintype "passive"))
      (node (ref "U10") (pin "12") (pinfunction "1B8_12") (pintype "passive"))
    )
    (net (code "78") (name "Net-(U10-2B1)") (class "Default")
      (node (ref "JP3") (pin "1") (pinfunction "1_1") (pintype "passive"))
      (node (ref "U10") (pin "13") (pinfunction "2B1_13") (pintype "passive"))
    )
    (net (code "79") (name "Net-(U10-2B2)") (class "Default")
      (node (ref "JP3") (pin "3") (pinfunction "3_3") (pintype "passive"))
      (node (ref "U10") (pin "14") (pinfunction "2B2_14") (pintype "passive"))
    )
    (net (code "80") (name "Net-(U10-2B3)") (class "Default")
      (node (ref "JP3") (pin "5") (pinfunction "5_5") (pintype "passive"))
      (node (ref "U10") (pin "16") (pinfunction "2B3_16") (pintype "passive"))
    )
    (net (code "81") (name "Net-(U10-2B4)") (class "Default")
      (node (ref "JP3") (pin "7") (pinfunction "7_7") (pintype "passive"))
      (node (ref "U10") (pin "17") (pinfunction "2B4_17") (pintype "passive"))
    )
    (net (code "82") (name "Net-(U10-2B5)") (class "Default")
      (node (ref "JP3") (pin "9") (pinfunction "9_9") (pintype "passive"))
      (node (ref "U10") (pin "19") (pinfunction "2B5_19") (pintype "passive"))
    )
    (net (code "83") (name "Net-(U10-2B6)") (class "Default")
      (node (ref "JP3") (pin "11") (pinfunction "11_11") (pintype "passive"))
      (node (ref "U10") (pin "20") (pinfunction "2B6_20") (pintype "passive"))
    )
    (net (code "84") (name "Net-(U10-2B7)") (class "Default")
      (node (ref "JP3") (pin "13") (pinfunction "13_13") (pintype "passive"))
      (node (ref "U10") (pin "22") (pinfunction "2B7_22") (pintype "passive"))
    )
    (net (code "85") (name "Net-(U10-2B8)") (class "Default")
      (node (ref "JP3") (pin "15") (pinfunction "15_15") (pintype "passive"))
      (node (ref "U10") (pin "23") (pinfunction "2B8_23") (pintype "passive"))
    )
    (net (code "86") (name "Net-(U11-1B1)") (class "Default")
      (node (ref "JP2") (pin "1") (pinfunction "1_1") (pintype "passive"))
      (node (ref "U11") (pin "2") (pinfunction "1B1_2") (pintype "passive"))
    )
    (net (code "87") (name "Net-(U11-1B2)") (class "Default")
      (node (ref "JP2") (pin "3") (pinfunction "3_3") (pintype "passive"))
      (node (ref "U11") (pin "3") (pinfunction "1B2_3") (pintype "passive"))
    )
    (net (code "88") (name "Net-(U11-1B3)") (class "Default")
      (node (ref "JP2") (pin "5") (pinfunction "5_5") (pintype "passive"))
      (node (ref "U11") (pin "5") (pinfunction "1B3_5") (pintype "passive"))
    )
    (net (code "89") (name "Net-(U11-1B4)") (class "Default")
      (node (ref "JP2") (pin "7") (pinfunction "7_7") (pintype "passive"))
      (node (ref "U11") (pin "6") (pinfunction "1B4_6") (pintype "passive"))
    )
    (net (code "90") (name "Net-(U11-1B5)") (class "Default")
      (node (ref "JP2") (pin "9") (pinfunction "9_9") (pintype "passive"))
      (node (ref "U11") (pin "8") (pinfunction "1B5_8") (pintype "passive"))
    )
    (net (code "91") (name "Net-(U11-1B6)") (class "Default")
      (node (ref "JP2") (pin "11") (pinfunction "11_11") (pintype "passive"))
      (node (ref "U11") (pin "9") (pinfunction "1B6_9") (pintype "passive"))
    )
    (net (code "92") (name "Net-(U11-1B7)") (class "Default")
      (node (ref "JP2") (pin "13") (pinfunction "13_13") (pintype "passive"))
      (node (ref "U11") (pin "11") (pinfunction "1B7_11") (pintype "passive"))
    )
    (net (code "93") (name "Net-(U11-1B8)") (class "Default")
      (node (ref "JP2") (pin "15") (pinfunction "15_15") (pintype "passive"))
      (node (ref "U11") (pin "12") (pinfunction "1B8_12") (pintype "passive"))
    )
    (net (code "94") (name "Net-(U11-2B1)") (class "Default")
      (node (ref "JP4") (pin "1") (pinfunction "1_1") (pintype "passive"))
      (node (ref "U11") (pin "13") (pinfunction "2B1_13") (pintype "passive"))
    )
    (net (code "95") (name "Net-(U11-2B2)") (class "Default")
      (node (ref "JP4") (pin "3") (pinfunction "3_3") (pintype "passive"))
      (node (ref "U11") (pin "14") (pinfunction "2B2_14") (pintype "passive"))
    )
    (net (code "96") (name "Net-(U11-2B3)") (class "Default")
      (node (ref "JP4") (pin "5") (pinfunction "5_5") (pintype "passive"))
      (node (ref "U11") (pin "16") (pinfunction "2B3_16") (pintype "passive"))
    )
    (net (code "97") (name "Net-(U11-2B4)") (class "Default")
      (node (ref "JP4") (pin "7") (pinfunction "7_7") (pintype "passive"))
      (node (ref "U11") (pin "17") (pinfunction "2B4_17") (pintype "passive"))
    )
    (net (code "98") (name "Net-(U11-2B5)") (class "Default")
      (node (ref "JP4") (pin "9") (pinfunction "9_9") (pintype "passive"))
      (node (ref "U11") (pin "19") (pinfunction "2B5_19") (pintype "passive"))
    )
    (net (code "99") (name "Net-(U11-2B6)") (class "Default")
      (node (ref "JP4") (pin "11") (pinfunction "11_11") (pintype "passive"))
      (node (ref "U11") (pin "20") (pinfunction "2B6_20") (pintype "passive"))
    )
    (net (code "100") (name "Net-(U11-2B7)") (class "Default")
      (node (ref "JP4") (pin "13") (pinfunction "13_13") (pintype "passive"))
      (node (ref "U11") (pin "22") (pinfunction "2B7_22") (pintype "passive"))
    )
    (net (code "101") (name "Net-(U11-2B8)") (class "Default")
      (node (ref "JP4") (pin "15") (pinfunction "15_15") (pintype "passive"))
      (node (ref "U11") (pin "23") (pinfunction "2B8_23") (pintype "passive"))
    )
    (net (code "102") (name "Net-(U16-1B1)") (class "Default")
      (node (ref "JP5") (pin "1") (pinfunction "1_1") (pintype "passive"))
      (node (ref "U16") (pin "2") (pinfunction "1B1_2") (pintype "passive"))
    )
    (net (code "103") (name "Net-(U16-1B2)") (class "Default")
      (node (ref "JP5") (pin "3") (pinfunction "3_3") (pintype "passive"))
      (node (ref "U16") (pin "3") (pinfunction "1B2_3") (pintype "passive"))
    )
    (net (code "104") (name "Net-(U16-1B3)") (class "Default")
      (node (ref "JP5") (pin "5") (pinfunction "5_5") (pintype "passive"))
      (node (ref "U16") (pin "5") (pinfunction "1B3_5") (pintype "passive"))
    )
    (net (code "105") (name "Net-(U16-1B4)") (class "Default")
      (node (ref "JP5") (pin "7") (pinfunction "7_7") (pintype "passive"))
      (node (ref "U16") (pin "6") (pinfunction "1B4_6") (pintype "passive"))
    )
    (net (code "106") (name "Net-(U16-1B5)") (class "Default")
      (node (ref "JP5") (pin "9") (pinfunction "9_9") (pintype "passive"))
      (node (ref "U16") (pin "8") (pinfunction "1B5_8") (pintype "passive"))
    )
    (net (code "107") (name "Net-(U16-1B6)") (class "Default")
      (node (ref "JP5") (pin "11") (pinfunction "11_11") (pintype "passive"))
      (node (ref "U16") (pin "9") (pinfunction "1B6_9") (pintype "passive"))
    )
    (net (code "108") (name "Net-(U16-1B7)") (class "Default")
      (node (ref "JP5") (pin "13") (pinfunction "13_13") (pintype "passive"))
      (node (ref "U16") (pin "11") (pinfunction "1B7_11") (pintype "passive"))
    )
    (net (code "109") (name "Net-(U16-1B8)") (class "Default")
      (node (ref "JP5") (pin "15") (pinfunction "15_15") (pintype "passive"))
      (node (ref "U16") (pin "12") (pinfunction "1B8_12") (pintype "passive"))
    )
    (net (code "110") (name "Net-(U16-2B1)") (class "Default")
      (node (ref "JP7") (pin "1") (pinfunction "1_1") (pintype "passive"))
      (node (ref "U16") (pin "13") (pinfunction "2B1_13") (pintype "passive"))
    )
    (net (code "111") (name "Net-(U16-2B2)") (class "Default")
      (node (ref "JP7") (pin "3") (pinfunction "3_3") (pintype "passive"))
      (node (ref "U16") (pin "14") (pinfunction "2B2_14") (pintype "passive"))
    )
    (net (code "112") (name "Net-(U16-2B3)") (class "Default")
      (node (ref "JP7") (pin "5") (pinfunction "5_5") (pintype "passive"))
      (node (ref "U16") (pin "16") (pinfunction "2B3_16") (pintype "passive"))
    )
    (net (code "113") (name "Net-(U16-2B4)") (class "Default")
      (node (ref "JP7") (pin "7") (pinfunction "7_7") (pintype "passive"))
      (node (ref "U16") (pin "17") (pinfunction "2B4_17") (pintype "passive"))
    )
    (net (code "114") (name "Net-(U16-2B5)") (class "Default")
      (node (ref "JP7") (pin "9") (pinfunction "9_9") (pintype "passive"))
      (node (ref "U16") (pin "19") (pinfunction "2B5_19") (pintype "passive"))
    )
    (net (code "115") (name "Net-(U16-2B6)") (class "Default")
      (node (ref "JP7") (pin "11") (pinfunction "11_11") (pintype "passive"))
      (node (ref "U16") (pin "20") (pinfunction "2B6_20") (pintype "passive"))
    )
    (net (code "116") (name "Net-(U16-2B7)") (class "Default")
      (node (ref "JP7") (pin "13") (pinfunction "13_13") (pintype "passive"))
      (node (ref "U16") (pin "22") (pinfunction "2B7_22") (pintype "passive"))
    )
    (net (code "117") (name "Net-(U16-2B8)") (class "Default")
      (node (ref "JP7") (pin "15") (pinfunction "15_15") (pintype "passive"))
      (node (ref "U16") (pin "23") (pinfunction "2B8_23") (pintype "passive"))
    )
    (net (code "118") (name "Net-(U17-1B1)") (class "Default")
      (node (ref "JP6") (pin "1") (pinfunction "1_1") (pintype "passive"))
      (node (ref "U17") (pin "2") (pinfunction "1B1_2") (pintype "passive"))
    )
    (net (code "119") (name "Net-(U17-1B2)") (class "Default")
      (node (ref "JP6") (pin "3") (pinfunction "3_3") (pintype "passive"))
      (node (ref "U17") (pin "3") (pinfunction "1B2_3") (pintype "passive"))
    )
    (net (code "120") (name "Net-(U17-1B3)") (class "Default")
      (node (ref "JP6") (pin "5") (pinfunction "5_5") (pintype "passive"))
      (node (ref "U17") (pin "5") (pinfunction "1B3_5") (pintype "passive"))
    )
    (net (code "121") (name "Net-(U17-1B4)") (class "Default")
      (node (ref "JP6") (pin "7") (pinfunction "7_7") (pintype "passive"))
      (node (ref "U17") (pin "6") (pinfunction "1B4_6") (pintype "passive"))
    )
    (net (code "122") (name "Net-(U17-1B5)") (class "Default")
      (node (ref "JP6") (pin "9") (pinfunction "9_9") (pintype "passive"))
      (node (ref "U17") (pin "8") (pinfunction "1B5_8") (pintype "passive"))
    )
    (net (code "123") (name "Net-(U17-1B6)") (class "Default")
      (node (ref "JP6") (pin "11") (pinfunction "11_11") (pintype "passive"))
      (node (ref "U17") (pin "9") (pinfunction "1B6_9") (pintype "passive"))
    )
    (net (code "124") (name "Net-(U17-1B7)") (class "Default")
      (node (ref "JP6") (pin "13") (pinfunction "13_13") (pintype "passive"))
      (node (ref "U17") (pin "11") (pinfunction "1B7_11") (pintype "passive"))
    )
    (net (code "125") (name "Net-(U17-1B8)") (class "Default")
      (node (ref "JP6") (pin "15") (pinfunction "15_15") (pintype "passive"))
      (node (ref "U17") (pin "12") (pinfunction "1B8_12") (pintype "passive"))
    )
    (net (code "126") (name "Net-(U17-2B1)") (class "Default")
      (node (ref "JP8") (pin "1") (pinfunction "1_1") (pintype "passive"))
      (node (ref "U17") (pin "13") (pinfunction "2B1_13") (pintype "passive"))
    )
    (net (code "127") (name "Net-(U17-2B2)") (class "Default")
      (node (ref "JP8") (pin "3") (pinfunction "3_3") (pintype "passive"))
      (node (ref "U17") (pin "14") (pinfunction "2B2_14") (pintype "passive"))
    )
    (net (code "128") (name "Net-(U17-2B3)") (class "Default")
      (node (ref "JP8") (pin "5") (pinfunction "5_5") (pintype "passive"))
      (node (ref "U17") (pin "16") (pinfunction "2B3_16") (pintype "passive"))
    )
    (net (code "129") (name "Net-(U17-2B4)") (class "Default")
      (node (ref "JP8") (pin "7") (pinfunction "7_7") (pintype "passive"))
      (node (ref "U17") (pin "17") (pinfunction "2B4_17") (pintype "passive"))
    )
    (net (code "130") (name "Net-(U17-2B5)") (class "Default")
      (node (ref "JP8") (pin "9") (pinfunction "9_9") (pintype "passive"))
      (node (ref "U17") (pin "19") (pinfunction "2B5_19") (pintype "passive"))
    )
    (net (code "131") (name "Net-(U17-2B6)") (class "Default")
      (node (ref "JP8") (pin "11") (pinfunction "11_11") (pintype "passive"))
      (node (ref "U17") (pin "20") (pinfunction "2B6_20") (pintype "passive"))
    )
    (net (code "132") (name "Net-(U17-2B7)") (class "Default")
      (node (ref "JP8") (pin "13") (pinfunction "13_13") (pintype "passive"))
      (node (ref "U17") (pin "22") (pinfunction "2B7_22") (pintype "passive"))
    )
    (net (code "133") (name "Net-(U17-2B8)") (class "Default")
      (node (ref "JP8") (pin "15") (pinfunction "15_15") (pintype "passive"))
      (node (ref "U17") (pin "23") (pinfunction "2B8_23") (pintype "passive"))
    )
    (net (code "134") (name "unconnected-(U1B-IO_L27N_0-PadE6)") (class "Default")
      (node (ref "U1") (pin "E6") (pinfunction "IO_L27N_0_E6") (pintype "input"))
    )
    (net (code "135") (name "unconnected-(U1B-IO_L31P_0{slash}VREF_0-PadC8)") (class "Default")
      (node (ref "U1") (pin "C8") (pinfunction "IO_L31P_0/VREF_0_C8") (pintype "input"))
    )
    (net (code "136") (name "unconnected-(U1G-IO_L28P_5{slash}D7-PadM6)") (class "Default")
      (node (ref "U1") (pin "M6") (pinfunction "IO_L28P_5/D7_M6") (pintype "input"))
    )
    (net (code "137") (name "unconnected-(U1G-IO_L30P_5-PadM7)") (class "Default")
      (node (ref "U1") (pin "M7") (pinfunction "IO_L30P_5_M7") (pintype "input"))
    )
    (net (code "138") (name "unconnected-(U1G-IO_L32P_5{slash}GCLK2-PadN8)") (class "Default")
      (node (ref "U1") (pin "N8") (pinfunction "IO_L32P_5/GCLK2_N8") (pintype "input"))
    )
    (net (code "139") (name "unconnected-(U1G-IO{slash}VREF_5-PadT8)") (class "Default")
      (node (ref "U1") (pin "T8") (pinfunction "IO/VREF_5_T8") (pintype "input"))
    )
    (net (code "140") (name "unconnected-(U1H-IO_L19N_6-PadM4)") (class "Default")
      (node (ref "U1") (pin "M4") (pinfunction "IO_L19N_6_M4") (pintype "input"))
    )
    (net (code "141") (name "unconnected-(U1H-IO_L21N_6-PadL5)") (class "Default")
      (node (ref "U1") (pin "L5") (pinfunction "IO_L21N_6_L5") (pintype "input"))
    )
    (net (code "142") (name "unconnected-(U1H-IO_L21P_6-PadL4)") (class "Default")
      (node (ref "U1") (pin "L4") (pinfunction "IO_L21P_6_L4") (pintype "input"))
    )
    (net (code "143") (name "unconnected-(U1H-IO_L23N_6-PadK5)") (class "Default")
      (node (ref "U1") (pin "K5") (pinfunction "IO_L23N_6_K5") (pintype "input"))
    )
    (net (code "144") (name "unconnected-(U1H-IO_L23P_6-PadK4)") (class "Default")
      (node (ref "U1") (pin "K4") (pinfunction "IO_L23P_6_K4") (pintype "input"))
    )
    (net (code "145") (name "unconnected-(U1H-IO_L39N_6-PadJ4)") (class "Default")
      (node (ref "U1") (pin "J4") (pinfunction "IO_L39N_6_J4") (pintype "input"))
    )
    (net (code "146") (name "unconnected-(U1H-IO_L39P_6-PadJ3)") (class "Default")
      (node (ref "U1") (pin "J3") (pinfunction "IO_L39P_6_J3") (pintype "input"))
    )
    (net (code "147") (name "unconnected-(U1I-IO_L16P_7{slash}VREF_7-PadC3)") (class "Default")
      (node (ref "U1") (pin "C3") (pinfunction "IO_L16P_7/VREF_7_C3") (pintype "input"))
    )
    (net (code "148") (name "unconnected-(U1I-IO_L19N_7{slash}VREF_7-PadE3)") (class "Default")
      (node (ref "U1") (pin "E3") (pinfunction "IO_L19N_7/VREF_7_E3") (pintype "input"))
    )
    (net (code "149") (name "unconnected-(U1I-IO_L21P_7-PadE4)") (class "Default")
      (node (ref "U1") (pin "E4") (pinfunction "IO_L21P_7_E4") (pintype "input"))
    )
    (net (code "150") (name "unconnected-(U1I-IO_L23N_7-PadG5)") (class "Default")
      (node (ref "U1") (pin "G5") (pinfunction "IO_L23N_7_G5") (pintype "input"))
    )
    (net (code "151") (name "unconnected-(U1I-IO_L23P_7-PadF5)") (class "Default")
      (node (ref "U1") (pin "F5") (pinfunction "IO_L23P_7_F5") (pintype "input"))
    )
    (net (code "152") (name "unconnected-(U1I-IO_L39N_7-PadH3)") (class "Default")
      (node (ref "U1") (pin "H3") (pinfunction "IO_L39N_7_H3") (pintype "input"))
    )
    (net (code "153") (name "unconnected-(U1I-IO_L39P_7-PadH4)") (class "Default")
      (node (ref "U1") (pin "H4") (pinfunction "IO_L39P_7_H4") (pintype "input"))
    )
  )
)
